# Costume_Controller_Base_Board.net
KiCad netlist of a schematic drawn in EAGLE
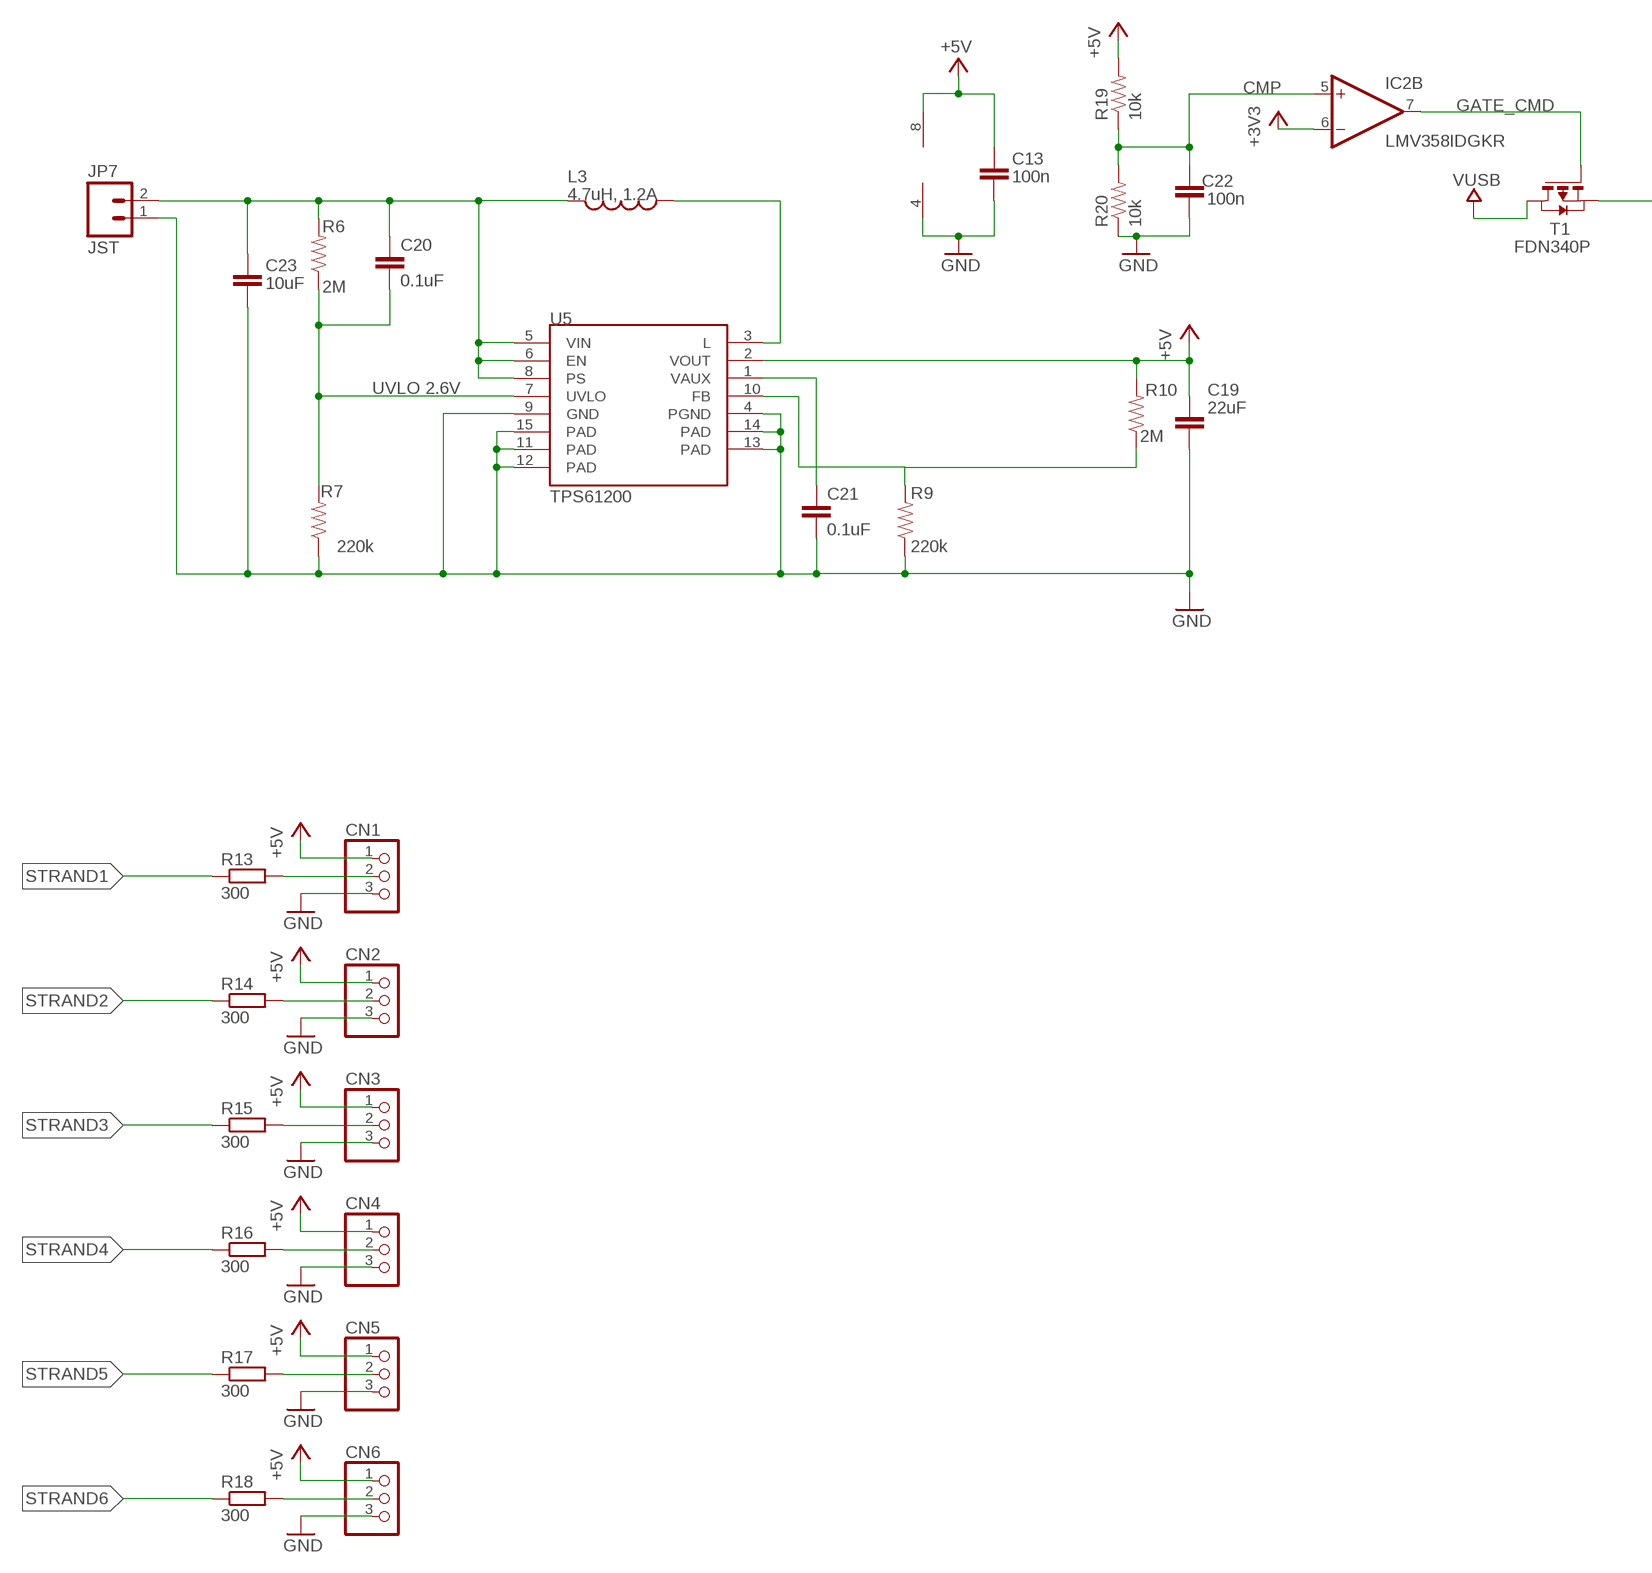
[diagram p0: schematic, sheet 1, part 1 of 2]
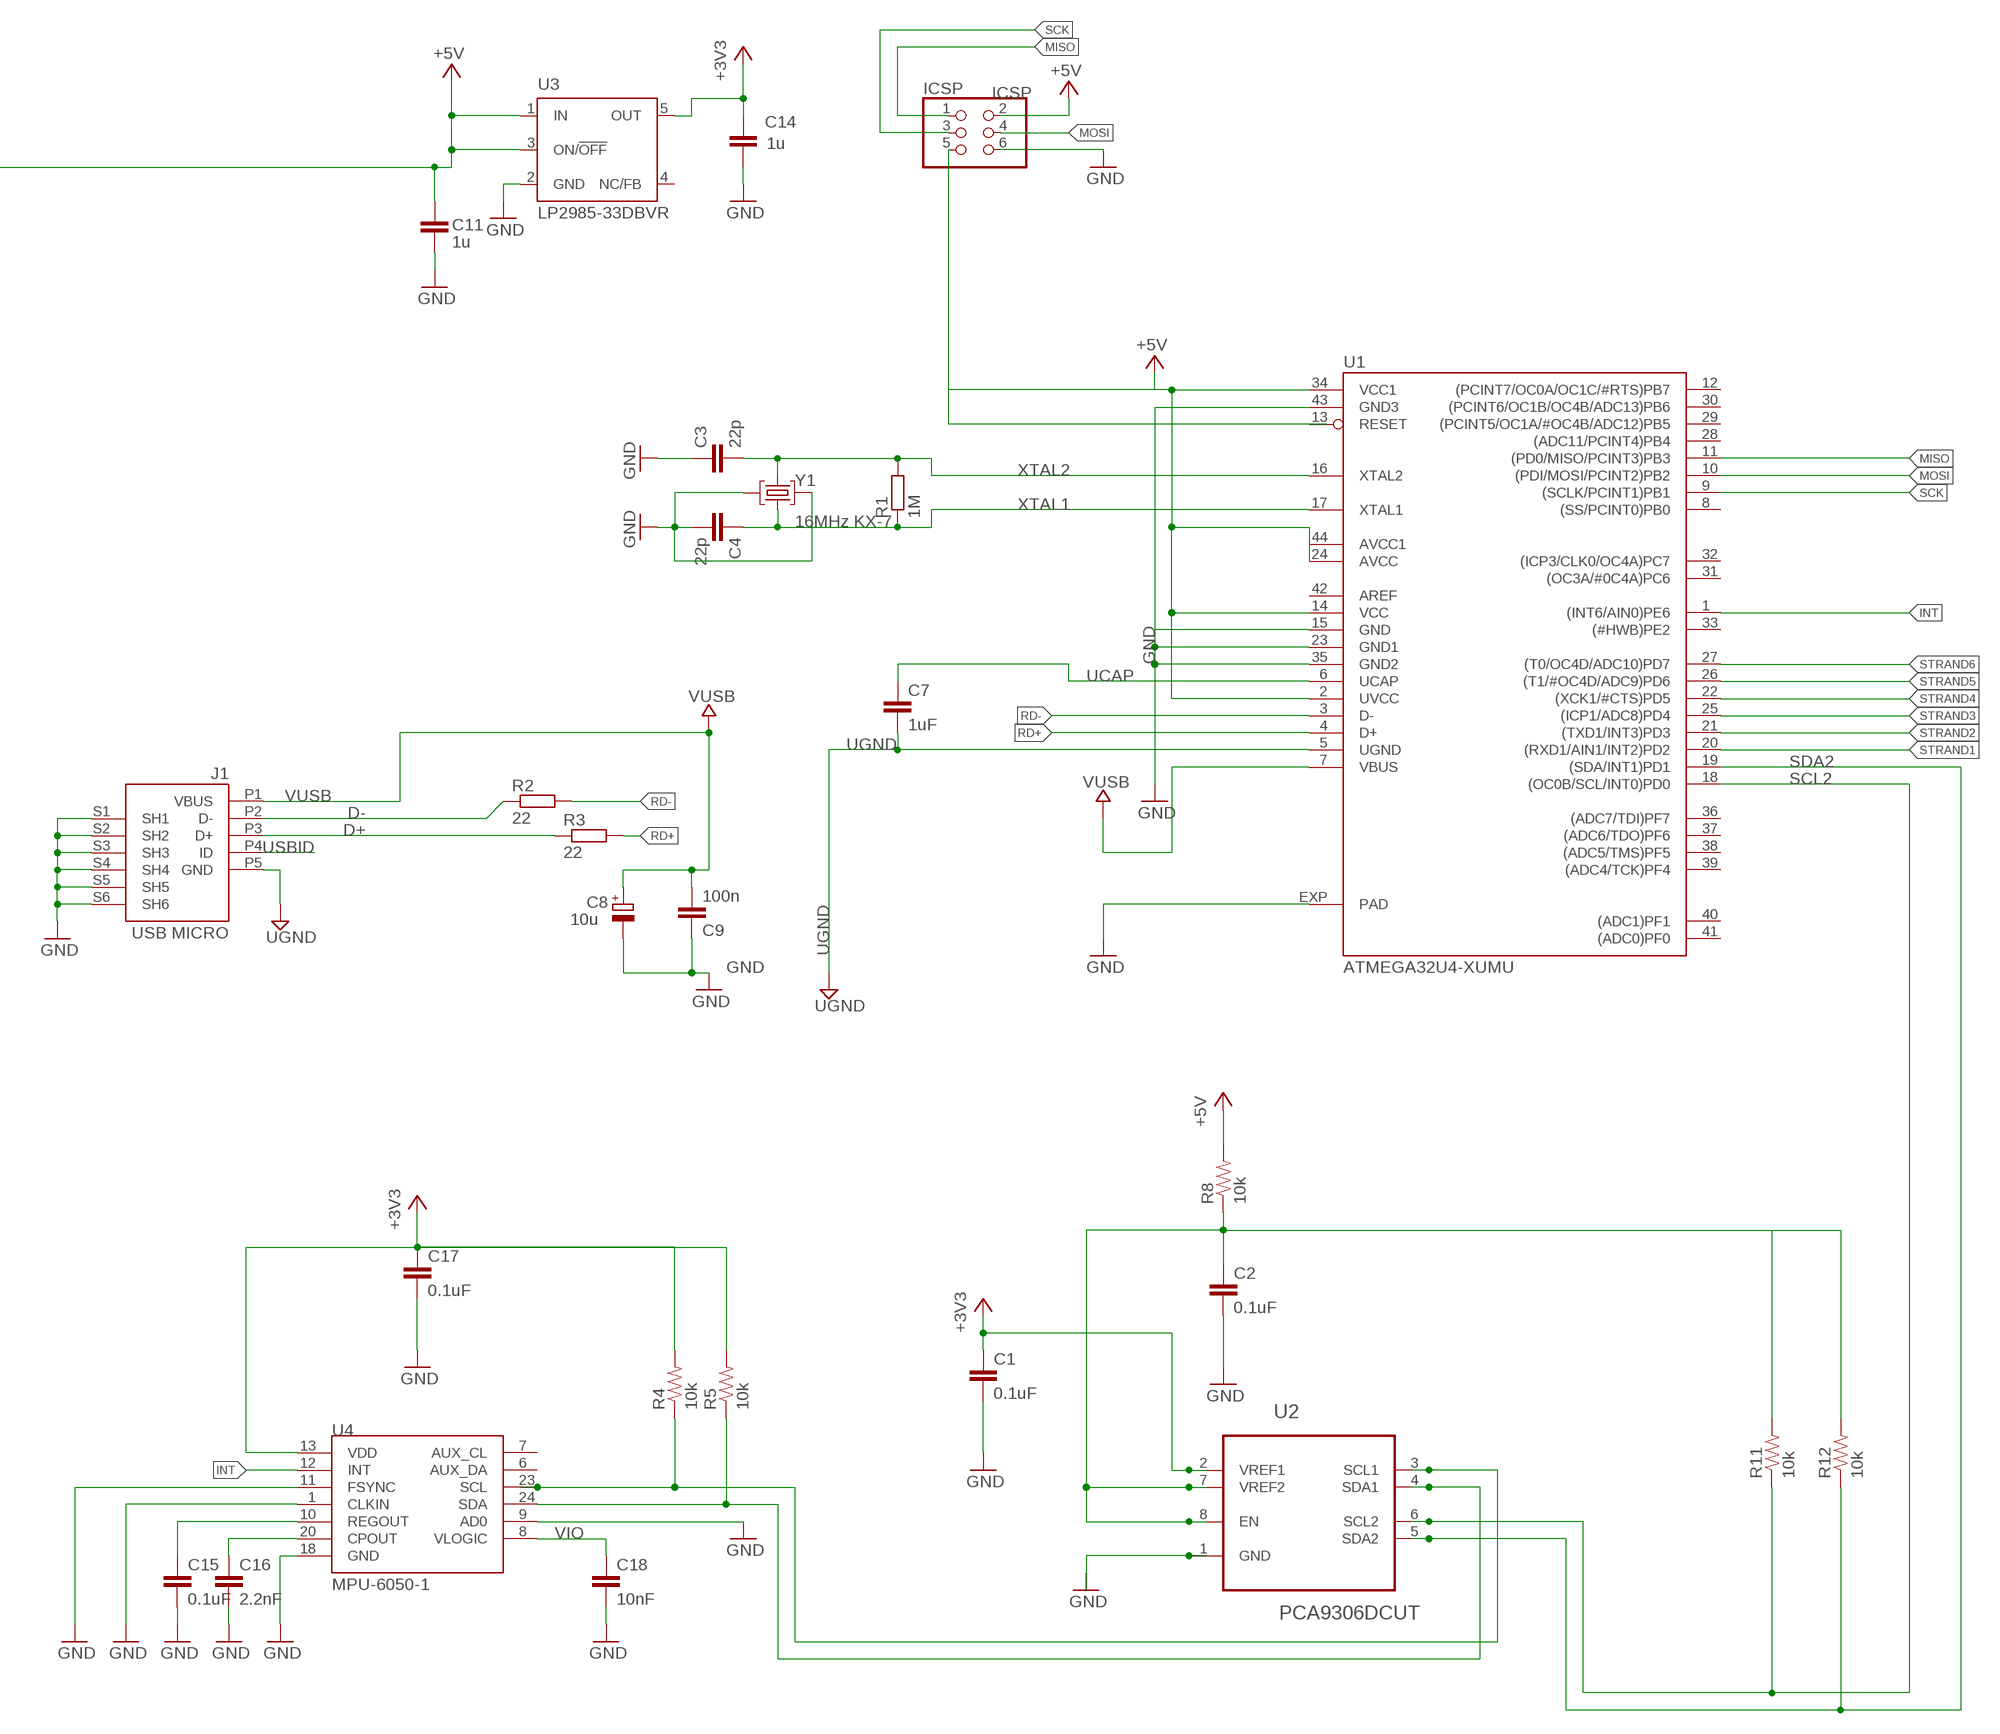
[diagram p1: schematic, sheet 1, part 2 of 2]

(export (version "E")
  (design (tool "Eeschema 10.0.6"))
  (components
    (comp (ref "C1")
      (value "0.1uF")
      (footprint "eagle-import:0603-CAP")
      (libsource (lib "eagle-import") (part "CAP0603-CAP"))
    )
    (comp (ref "C2")
      (value "0.1uF")
      (footprint "eagle-import:0603-CAP")
      (libsource (lib "eagle-import") (part "CAP0603-CAP"))
    )
    (comp (ref "C3")
      (value "22p")
      (footprint "eagle-import:C0603-ROUND")
      (libsource (lib "eagle-import") (part "C-EUC0603"))
    )
    (comp (ref "C4")
      (value "22p")
      (footprint "eagle-import:C0603-ROUND")
      (libsource (lib "eagle-import") (part "C-EUC0603"))
    )
    (comp (ref "C7")
      (value "1uF")
      (footprint "eagle-import:C0603-ROUND")
      (libsource (lib "eagle-import") (part "C-EUC0603"))
    )
    (comp (ref "C8")
      (value "10u")
      (footprint "eagle-import:SMC_B")
      (libsource (lib "eagle-import") (part "CPOL-EUSMCB"))
    )
    (comp (ref "C9")
      (value "100n")
      (footprint "eagle-import:C0603-ROUND")
      (libsource (lib "eagle-import") (part "C-EUC0603"))
    )
    (comp (ref "C11")
      (value "1u")
      (footprint "eagle-import:C0603-ROUND")
      (libsource (lib "eagle-import") (part "C-EUC0603"))
    )
    (comp (ref "C13")
      (value "100n")
      (footprint "eagle-import:C0603-ROUND")
      (libsource (lib "eagle-import") (part "C-EUC0603"))
    )
    (comp (ref "C14")
      (value "1u")
      (footprint "eagle-import:C0603-ROUND")
      (libsource (lib "eagle-import") (part "C-EUC0603"))
    )
    (comp (ref "C15")
      (value "0.1uF")
      (footprint "eagle-import:0603-CAP")
      (libsource (lib "eagle-import") (part "CAP0603-CAP"))
    )
    (comp (ref "C16")
      (value "2.2nF")
      (footprint "eagle-import:0603-CAP")
      (libsource (lib "eagle-import") (part "CAP0603-CAP"))
    )
    (comp (ref "C17")
      (value "0.1uF")
      (footprint "eagle-import:0603-CAP")
      (libsource (lib "eagle-import") (part "CAP0603-CAP"))
    )
    (comp (ref "C18")
      (value "10nF")
      (footprint "eagle-import:0603-CAP")
      (libsource (lib "eagle-import") (part "CAP0603-CAP"))
    )
    (comp (ref "C19")
      (value "22uF")
      (footprint "eagle-import:C0603")
      (libsource (lib "eagle-import") (part "resistor_C-EUC0603"))
    )
    (comp (ref "C20")
      (value "0.1uF")
      (footprint "eagle-import:0603-CAP")
      (libsource (lib "eagle-import") (part "CAP0603-CAP"))
    )
    (comp (ref "C21")
      (value "0.1uF")
      (footprint "eagle-import:0603-CAP")
      (libsource (lib "eagle-import") (part "CAP0603-CAP"))
    )
    (comp (ref "C22")
      (value "100n")
      (footprint "eagle-import:C0603-ROUND")
      (libsource (lib "eagle-import") (part "C-EUC0603"))
    )
    (comp (ref "C23")
      (value "10uF")
      (footprint "eagle-import:1206")
      (libsource (lib "eagle-import") (part "CAP1206"))
    )
    (comp (ref "CN1")
      (value "JST_3PIN")
      (footprint "eagle-import:JSTPH3")
      (libsource (lib "eagle-import") (part "JST_3PIN"))
    )
    (comp (ref "CN2")
      (value "JST_3PIN")
      (footprint "eagle-import:JSTPH3")
      (libsource (lib "eagle-import") (part "JST_3PIN"))
    )
    (comp (ref "CN3")
      (value "JST_3PIN")
      (footprint "eagle-import:JSTPH3")
      (libsource (lib "eagle-import") (part "JST_3PIN"))
    )
    (comp (ref "CN4")
      (value "JST_3PIN")
      (footprint "eagle-import:JSTPH3")
      (libsource (lib "eagle-import") (part "JST_3PIN"))
    )
    (comp (ref "CN5")
      (value "JST_3PIN")
      (footprint "eagle-import:JSTPH3")
      (libsource (lib "eagle-import") (part "JST_3PIN"))
    )
    (comp (ref "CN6")
      (value "JST_3PIN")
      (footprint "eagle-import:JSTPH3")
      (libsource (lib "eagle-import") (part "JST_3PIN"))
    )
    (comp (ref "IC2")
      (value "LMV358IDGKR")
      (footprint "eagle-import:MSOP08")
      (libsource (lib "eagle-import") (part "LMV358?MMX"))
    )
    (comp (ref "ICSP")
      (value "ICSP")
      (footprint "eagle-import:2X03")
      (libsource (lib "eagle-import") (part "PINHD-2X3"))
    )
    (comp (ref "J1")
      (value "USB MICRO")
      (footprint "eagle-import:CON2_USB_MICRO_B_AT")
      (libsource (lib "eagle-import") (part "MYCON2_USB-MINI-B"))
    )
    (comp (ref "JP7")
      (value "JST")
      (footprint "eagle-import:JST-2-SMD")
      (libsource (lib "eagle-import") (part "M02-JST-2MM-SMT"))
    )
    (comp (ref "L3")
      (value "4.7uH, 1.2A")
      (footprint "eagle-import:CDRH2D09")
      (libsource (lib "eagle-import") (part "INDUCTOR."))
    )
    (comp (ref "R1")
      (value "1M")
      (footprint "eagle-import:R0603")
      (libsource (lib "eagle-import") (part "R-EU_R0603"))
    )
    (comp (ref "R2")
      (value "22")
      (footprint "eagle-import:R0603")
      (libsource (lib "eagle-import") (part "R-EU_R0603"))
    )
    (comp (ref "R3")
      (value "22")
      (footprint "eagle-import:R0603")
      (libsource (lib "eagle-import") (part "R-EU_R0603"))
    )
    (comp (ref "R4")
      (value "10k")
      (footprint "eagle-import:0603-RES")
      (libsource (lib "eagle-import") (part "RESISTOR0603-RES"))
    )
    (comp (ref "R5")
      (value "10k")
      (footprint "eagle-import:0603-RES")
      (libsource (lib "eagle-import") (part "RESISTOR0603-RES"))
    )
    (comp (ref "R6")
      (value "2M")
      (footprint "eagle-import:0603-RES")
      (libsource (lib "eagle-import") (part "RESISTOR0603-RES"))
    )
    (comp (ref "R7")
      (value "220k")
      (footprint "eagle-import:0603-RES")
      (libsource (lib "eagle-import") (part "RESISTOR0603-RES"))
    )
    (comp (ref "R8")
      (value "10k")
      (footprint "eagle-import:0603-RES")
      (libsource (lib "eagle-import") (part "RESISTOR0603-RES"))
    )
    (comp (ref "R9")
      (value "220k")
      (footprint "eagle-import:0603-RES")
      (libsource (lib "eagle-import") (part "RESISTOR0603-RES"))
    )
    (comp (ref "R10")
      (value "2M")
      (footprint "eagle-import:0603-RES")
      (libsource (lib "eagle-import") (part "RESISTOR0603-RES"))
    )
    (comp (ref "R11")
      (value "10k")
      (footprint "eagle-import:0603-RES")
      (libsource (lib "eagle-import") (part "RESISTOR0603-RES"))
    )
    (comp (ref "R12")
      (value "10k")
      (footprint "eagle-import:0603-RES")
      (libsource (lib "eagle-import") (part "RESISTOR0603-RES"))
    )
    (comp (ref "R13")
      (value "300")
      (footprint "eagle-import:R0603")
      (libsource (lib "eagle-import") (part "R-EU_R0603"))
    )
    (comp (ref "R14")
      (value "300")
      (footprint "eagle-import:R0603")
      (libsource (lib "eagle-import") (part "R-EU_R0603"))
    )
    (comp (ref "R15")
      (value "300")
      (footprint "eagle-import:R0603")
      (libsource (lib "eagle-import") (part "R-EU_R0603"))
    )
    (comp (ref "R16")
      (value "300")
      (footprint "eagle-import:R0603")
      (libsource (lib "eagle-import") (part "R-EU_R0603"))
    )
    (comp (ref "R17")
      (value "300")
      (footprint "eagle-import:R0603")
      (libsource (lib "eagle-import") (part "R-EU_R0603"))
    )
    (comp (ref "R18")
      (value "300")
      (footprint "eagle-import:R0603")
      (libsource (lib "eagle-import") (part "R-EU_R0603"))
    )
    (comp (ref "R19")
      (value "10k")
      (footprint "eagle-import:0603-RES")
      (libsource (lib "eagle-import") (part "RESISTOR0603-RES"))
    )
    (comp (ref "R20")
      (value "10k")
      (footprint "eagle-import:0603-RES")
      (libsource (lib "eagle-import") (part "RESISTOR0603-RES"))
    )
    (comp (ref "T1")
      (value "FDN340P")
      (footprint "eagle-import:SOT-23")
      (libsource (lib "eagle-import") (part "PMOSSOT23"))
    )
    (comp (ref "U1")
      (value "ATMEGA32U4-XUMU")
      (footprint "eagle-import:QFN44ML7X7")
      (libsource (lib "eagle-import") (part "ATMEGA32U4-XUMU"))
    )
    (comp (ref "U2")
      (value "PCA9306DCUT")
      (footprint "eagle-import:SOP50P310X90-8N")
      (libsource (lib "eagle-import") (part "PCA9306DCUT"))
    )
    (comp (ref "U3")
      (value "LP2985-33DBVR")
      (footprint "eagle-import:SOT23-DBV")
      (libsource (lib "eagle-import") (part "LP2985-XXDBVR33"))
    )
    (comp (ref "U4")
      (value "MPU-6050-1")
      (footprint "eagle-import:QFN-24-4MM2")
      (libsource (lib "eagle-import") (part "MPU-6050-1"))
    )
    (comp (ref "U5")
      (value "TPS61200")
      (footprint "eagle-import:QFN-10_PAD")
      (libsource (lib "eagle-import") (part "TPS61200"))
    )
    (comp (ref "Y1")
      (value "16MHz KX-7")
      (footprint "eagle-import:CRYSTAL-3.2-2.5")
      (libsource (lib "eagle-import") (part "CRYSTAL-3.2-2.5"))
    )
  )
  (nets
    (net (code "1") (name "+3V3") (class "Default")
      (node (ref "C1") (pin "1") (pinfunction "1_1") (pintype "passive"))
      (node (ref "C14") (pin "2") (pinfunction "2_2") (pintype "passive"))
      (node (ref "C17") (pin "1") (pinfunction "1_1") (pintype "passive"))
      (node (ref "IC2") (pin "6") (pinfunction "-IN_6") (pintype "input"))
      (node (ref "R4") (pin "2") (pinfunction "2_2") (pintype "passive"))
      (node (ref "R5") (pin "2") (pinfunction "2_2") (pintype "passive"))
      (node (ref "U2") (pin "2") (pinfunction "VREF1_2") (pintype "power_in"))
      (node (ref "U3") (pin "5") (pinfunction "OUT_5") (pintype "passive"))
      (node (ref "U4") (pin "13") (pinfunction "VDD_13") (pintype "bidirectional"))
    )
    (net (code "2") (name "+5V") (class "Default")
      (node (ref "C11") (pin "2") (pinfunction "2_2") (pintype "passive"))
      (node (ref "C13") (pin "1") (pinfunction "1_1") (pintype "passive"))
      (node (ref "C19") (pin "1") (pinfunction "1_1") (pintype "passive"))
      (node (ref "CN1") (pin "1") (pinfunction "1_1") (pintype "passive"))
      (node (ref "CN2") (pin "1") (pinfunction "1_1") (pintype "passive"))
      (node (ref "CN3") (pin "1") (pinfunction "1_1") (pintype "passive"))
      (node (ref "CN4") (pin "1") (pinfunction "1_1") (pintype "passive"))
      (node (ref "CN5") (pin "1") (pinfunction "1_1") (pintype "passive"))
      (node (ref "CN6") (pin "1") (pinfunction "1_1") (pintype "passive"))
      (node (ref "IC2") (pin "8") (pinfunction "V+_8") (pintype "power_in"))
      (node (ref "ICSP") (pin "2") (pinfunction "2_2") (pintype "passive"))
      (node (ref "ICSP") (pin "5") (pinfunction "5_5") (pintype "passive"))
      (node (ref "R10") (pin "2") (pinfunction "2_2") (pintype "passive"))
      (node (ref "R19") (pin "2") (pinfunction "2_2") (pintype "passive"))
      (node (ref "R8") (pin "2") (pinfunction "2_2") (pintype "passive"))
      (node (ref "T1") (pin "2") (pinfunction "S_2") (pintype "passive"))
      (node (ref "U1") (pin "14") (pinfunction "VCC_14") (pintype "power_in"))
      (node (ref "U1") (pin "2") (pinfunction "UVCC_2") (pintype "power_in"))
      (node (ref "U1") (pin "24") (pinfunction "AVCC_24") (pintype "power_in"))
      (node (ref "U1") (pin "34") (pinfunction "VCC1_34") (pintype "power_in"))
      (node (ref "U1") (pin "44") (pinfunction "AVCC1_44") (pintype "power_in"))
      (node (ref "U3") (pin "1") (pinfunction "IN_1") (pintype "input"))
      (node (ref "U3") (pin "3") (pinfunction "ON/~{OFF}_3") (pintype "input"))
      (node (ref "U5") (pin "2") (pinfunction "VOUT_2") (pintype "passive"))
    )
    (net (code "3") (name "/AREF") (class "Default")
      (node (ref "U1") (pin "42") (pinfunction "AREF_42") (pintype "power_in"))
    )
    (net (code "4") (name "/CMP") (class "Default")
      (node (ref "C22") (pin "2") (pinfunction "2_2") (pintype "passive"))
      (node (ref "IC2") (pin "5") (pinfunction "+IN_5") (pintype "input"))
      (node (ref "R19") (pin "1") (pinfunction "1_1") (pintype "passive"))
      (node (ref "R20") (pin "2") (pinfunction "2_2") (pintype "passive"))
    )
    (net (code "5") (name "/D+") (class "Default")
      (node (ref "J1") (pin "P3") (pinfunction "D+_P3") (pintype "bidirectional"))
      (node (ref "R3") (pin "1") (pinfunction "1_1") (pintype "passive"))
    )
    (net (code "6") (name "/D-") (class "Default")
      (node (ref "J1") (pin "P2") (pinfunction "D-_P2") (pintype "bidirectional"))
      (node (ref "R2") (pin "1") (pinfunction "1_1") (pintype "passive"))
    )
    (net (code "7") (name "/GATE_CMD") (class "Default")
      (node (ref "IC2") (pin "7") (pinfunction "OUT_7") (pintype "output"))
      (node (ref "T1") (pin "3") (pinfunction "G_3") (pintype "passive"))
    )
    (net (code "8") (name "/SCL2") (class "Default")
      (node (ref "R11") (pin "1") (pinfunction "1_1") (pintype "passive"))
      (node (ref "U1") (pin "18") (pinfunction "(OC0B/SCL/INT0)PD0_18") (pintype "bidirectional"))
      (node (ref "U2") (pin "6") (pinfunction "SCL2_6") (pintype "bidirectional"))
    )
    (net (code "9") (name "/SDA2") (class "Default")
      (node (ref "R12") (pin "1") (pinfunction "1_1") (pintype "passive"))
      (node (ref "U1") (pin "19") (pinfunction "(SDA/INT1)PD1_19") (pintype "bidirectional"))
      (node (ref "U2") (pin "5") (pinfunction "SDA2_5") (pintype "bidirectional"))
    )
    (net (code "10") (name "/UCAP") (class "Default")
      (node (ref "C7") (pin "1") (pinfunction "1_1") (pintype "passive"))
      (node (ref "U1") (pin "6") (pinfunction "UCAP_6") (pintype "passive"))
    )
    (net (code "11") (name "/USBID") (class "Default")
      (node (ref "J1") (pin "P4") (pinfunction "ID_P4") (pintype "bidirectional"))
    )
    (net (code "12") (name "/VIO") (class "Default")
      (node (ref "C18") (pin "1") (pinfunction "1_1") (pintype "passive"))
      (node (ref "U4") (pin "8") (pinfunction "VLOGIC_8") (pintype "bidirectional"))
    )
    (net (code "13") (name "/XTAL1") (class "Default")
      (node (ref "C4") (pin "1") (pinfunction "1_1") (pintype "passive"))
      (node (ref "R1") (pin "1") (pinfunction "1_1") (pintype "passive"))
      (node (ref "U1") (pin "17") (pinfunction "XTAL1_17") (pintype "bidirectional"))
      (node (ref "Y1") (pin "1") (pinfunction "C1_1") (pintype "passive"))
    )
    (net (code "14") (name "/XTAL2") (class "Default")
      (node (ref "C3") (pin "2") (pinfunction "2_2") (pintype "passive"))
      (node (ref "R1") (pin "2") (pinfunction "2_2") (pintype "passive"))
      (node (ref "U1") (pin "16") (pinfunction "XTAL2_16") (pintype "bidirectional"))
      (node (ref "Y1") (pin "3") (pinfunction "C2_3") (pintype "passive"))
    )
    (net (code "15") (name "GND") (class "Default")
      (node (ref "C1") (pin "2") (pinfunction "2_2") (pintype "passive"))
      (node (ref "C11") (pin "1") (pinfunction "1_1") (pintype "passive"))
      (node (ref "C13") (pin "2") (pinfunction "2_2") (pintype "passive"))
      (node (ref "C14") (pin "1") (pinfunction "1_1") (pintype "passive"))
      (node (ref "C15") (pin "2") (pinfunction "2_2") (pintype "passive"))
      (node (ref "C16") (pin "2") (pinfunction "2_2") (pintype "passive"))
      (node (ref "C17") (pin "2") (pinfunction "2_2") (pintype "passive"))
      (node (ref "C18") (pin "2") (pinfunction "2_2") (pintype "passive"))
      (node (ref "C19") (pin "2") (pinfunction "2_2") (pintype "passive"))
      (node (ref "C2") (pin "2") (pinfunction "2_2") (pintype "passive"))
      (node (ref "C21") (pin "2") (pinfunction "2_2") (pintype "passive"))
      (node (ref "C22") (pin "1") (pinfunction "1_1") (pintype "passive"))
      (node (ref "C23") (pin "2") (pinfunction "2_2") (pintype "passive"))
      (node (ref "C3") (pin "1") (pinfunction "1_1") (pintype "passive"))
      (node (ref "C4") (pin "2") (pinfunction "2_2") (pintype "passive"))
      (node (ref "C8") (pin "-") (pinfunction "-_-") (pintype "passive"))
      (node (ref "C9") (pin "1") (pinfunction "1_1") (pintype "passive"))
      (node (ref "CN1") (pin "3") (pinfunction "3_3") (pintype "passive"))
      (node (ref "CN2") (pin "3") (pinfunction "3_3") (pintype "passive"))
      (node (ref "CN3") (pin "3") (pinfunction "3_3") (pintype "passive"))
      (node (ref "CN4") (pin "3") (pinfunction "3_3") (pintype "passive"))
      (node (ref "CN5") (pin "3") (pinfunction "3_3") (pintype "passive"))
      (node (ref "CN6") (pin "3") (pinfunction "3_3") (pintype "passive"))
      (node (ref "IC2") (pin "4") (pinfunction "V-_4") (pintype "power_in"))
      (node (ref "ICSP") (pin "6") (pinfunction "6_6") (pintype "passive"))
      (node (ref "J1") (pin "S1") (pinfunction "SH1_S1") (pintype "passive"))
      (node (ref "J1") (pin "S2") (pinfunction "SH2_S2") (pintype "passive"))
      (node (ref "J1") (pin "S3") (pinfunction "SH3_S3") (pintype "passive"))
      (node (ref "J1") (pin "S4") (pinfunction "SH4_S4") (pintype "passive"))
      (node (ref "J1") (pin "S5") (pinfunction "SH5_S5") (pintype "passive"))
      (node (ref "J1") (pin "S6") (pinfunction "SH6_S6") (pintype "passive"))
      (node (ref "JP7") (pin "1") (pinfunction "1_1") (pintype "passive"))
      (node (ref "R20") (pin "1") (pinfunction "1_1") (pintype "passive"))
      (node (ref "R7") (pin "1") (pinfunction "1_1") (pintype "passive"))
      (node (ref "R9") (pin "1") (pinfunction "1_1") (pintype "passive"))
      (node (ref "U1") (pin "15") (pinfunction "GND_15") (pintype "power_in"))
      (node (ref "U1") (pin "23") (pinfunction "GND1_23") (pintype "power_in"))
      (node (ref "U1") (pin "35") (pinfunction "GND2_35") (pintype "power_in"))
      (node (ref "U1") (pin "43") (pinfunction "GND3_43") (pintype "power_in"))
      (node (ref "U1") (pin "EXP") (pinfunction "PAD_EXP") (pintype "power_in"))
      (node (ref "U2") (pin "1") (pinfunction "GND_1") (pintype "passive"))
      (node (ref "U3") (pin "2") (pinfunction "GND_2") (pintype "power_in"))
      (node (ref "U4") (pin "1") (pinfunction "CLKIN_1") (pintype "bidirectional"))
      (node (ref "U4") (pin "11") (pinfunction "FSYNC_11") (pintype "bidirectional"))
      (node (ref "U4") (pin "18") (pinfunction "GND_18") (pintype "bidirectional"))
      (node (ref "U4") (pin "9") (pinfunction "AD0_9") (pintype "bidirectional"))
      (node (ref "U5") (pin "11") (pinfunction "PAD_11") (pintype "power_in"))
      (node (ref "U5") (pin "12") (pinfunction "PAD_12") (pintype "power_in"))
      (node (ref "U5") (pin "13") (pinfunction "PAD_13") (pintype "power_in"))
      (node (ref "U5") (pin "14") (pinfunction "PAD_14") (pintype "power_in"))
      (node (ref "U5") (pin "15") (pinfunction "PAD_15") (pintype "power_in"))
      (node (ref "U5") (pin "4") (pinfunction "PGND_4") (pintype "power_in"))
      (node (ref "U5") (pin "9") (pinfunction "GND_9") (pintype "power_in"))
      (node (ref "Y1") (pin "2") (pinfunction "GND_2") (pintype "passive"))
      (node (ref "Y1") (pin "4") (pinfunction "GND_4") (pintype "passive"))
    )
    (net (code "16") (name "INT") (class "Default")
      (node (ref "U1") (pin "1") (pinfunction "(INT6/AIN0)PE6_1") (pintype "bidirectional"))
      (node (ref "U4") (pin "12") (pinfunction "INT_12") (pintype "bidirectional"))
    )
    (net (code "17") (name "MISO") (class "Default")
      (node (ref "ICSP") (pin "1") (pinfunction "1_1") (pintype "passive"))
      (node (ref "U1") (pin "11") (pinfunction "(PD0/MISO/PCINT3)PB3_11") (pintype "bidirectional"))
    )
    (net (code "18") (name "MOSI") (class "Default")
      (node (ref "ICSP") (pin "4") (pinfunction "4_4") (pintype "passive"))
      (node (ref "U1") (pin "10") (pinfunction "(PDI/MOSI/PCINT2)PB2_10") (pintype "bidirectional"))
    )
    (net (code "19") (name "Net-(CN1-Pad2)") (class "Default")
      (node (ref "CN1") (pin "2") (pinfunction "2_2") (pintype "passive"))
      (node (ref "R13") (pin "2") (pinfunction "2_2") (pintype "passive"))
    )
    (net (code "20") (name "Net-(CN2-Pad2)") (class "Default")
      (node (ref "CN2") (pin "2") (pinfunction "2_2") (pintype "passive"))
      (node (ref "R14") (pin "2") (pinfunction "2_2") (pintype "passive"))
    )
    (net (code "21") (name "Net-(CN3-Pad2)") (class "Default")
      (node (ref "CN3") (pin "2") (pinfunction "2_2") (pintype "passive"))
      (node (ref "R15") (pin "2") (pinfunction "2_2") (pintype "passive"))
    )
    (net (code "22") (name "Net-(CN4-Pad2)") (class "Default")
      (node (ref "CN4") (pin "2") (pinfunction "2_2") (pintype "passive"))
      (node (ref "R16") (pin "2") (pinfunction "2_2") (pintype "passive"))
    )
    (net (code "23") (name "Net-(CN5-Pad2)") (class "Default")
      (node (ref "CN5") (pin "2") (pinfunction "2_2") (pintype "passive"))
      (node (ref "R17") (pin "2") (pinfunction "2_2") (pintype "passive"))
    )
    (net (code "24") (name "Net-(CN6-Pad2)") (class "Default")
      (node (ref "CN6") (pin "2") (pinfunction "2_2") (pintype "passive"))
      (node (ref "R18") (pin "2") (pinfunction "2_2") (pintype "passive"))
    )
    (net (code "25") (name "Net-(L3-1)") (class "Default")
      (node (ref "L3") (pin "P$1") (pinfunction "1_P$1") (pintype "passive"))
      (node (ref "U5") (pin "3") (pinfunction "L_3") (pintype "passive"))
    )
    (net (code "26") (name "Net-(L3-2)") (class "Default")
      (node (ref "C20") (pin "1") (pinfunction "1_1") (pintype "passive"))
      (node (ref "C23") (pin "1") (pinfunction "1_1") (pintype "passive"))
      (node (ref "JP7") (pin "2") (pinfunction "2_2") (pintype "passive"))
      (node (ref "L3") (pin "P$2") (pinfunction "2_P$2") (pintype "passive"))
      (node (ref "R6") (pin "2") (pinfunction "2_2") (pintype "passive"))
      (node (ref "U5") (pin "5") (pinfunction "VIN_5") (pintype "power_in"))
      (node (ref "U5") (pin "6") (pinfunction "EN_6") (pintype "input"))
      (node (ref "U5") (pin "8") (pinfunction "PS_8") (pintype "input"))
    )
    (net (code "27") (name "Net-(U2-EN)") (class "Default")
      (node (ref "C2") (pin "1") (pinfunction "1_1") (pintype "passive"))
      (node (ref "R11") (pin "2") (pinfunction "2_2") (pintype "passive"))
      (node (ref "R12") (pin "2") (pinfunction "2_2") (pintype "passive"))
      (node (ref "R8") (pin "1") (pinfunction "1_1") (pintype "passive"))
      (node (ref "U2") (pin "7") (pinfunction "VREF2_7") (pintype "power_in"))
      (node (ref "U2") (pin "8") (pinfunction "EN_8") (pintype "input"))
    )
    (net (code "28") (name "Net-(U2-SCL1)") (class "Default")
      (node (ref "R4") (pin "1") (pinfunction "1_1") (pintype "passive"))
      (node (ref "U2") (pin "3") (pinfunction "SCL1_3") (pintype "bidirectional"))
      (node (ref "U4") (pin "23") (pinfunction "SCL_23") (pintype "bidirectional"))
    )
    (net (code "29") (name "Net-(U2-SDA1)") (class "Default")
      (node (ref "R5") (pin "1") (pinfunction "1_1") (pintype "passive"))
      (node (ref "U2") (pin "4") (pinfunction "SDA1_4") (pintype "bidirectional"))
      (node (ref "U4") (pin "24") (pinfunction "SDA_24") (pintype "bidirectional"))
    )
    (net (code "30") (name "Net-(U4-CPOUT)") (class "Default")
      (node (ref "C16") (pin "1") (pinfunction "1_1") (pintype "passive"))
      (node (ref "U4") (pin "20") (pinfunction "CPOUT_20") (pintype "bidirectional"))
    )
    (net (code "31") (name "Net-(U4-REGOUT)") (class "Default")
      (node (ref "C15") (pin "1") (pinfunction "1_1") (pintype "passive"))
      (node (ref "U4") (pin "10") (pinfunction "REGOUT_10") (pintype "bidirectional"))
    )
    (net (code "32") (name "Net-(U5-FB)") (class "Default")
      (node (ref "R10") (pin "1") (pinfunction "1_1") (pintype "passive"))
      (node (ref "R9") (pin "2") (pinfunction "2_2") (pintype "passive"))
      (node (ref "U5") (pin "10") (pinfunction "FB_10") (pintype "passive"))
    )
    (net (code "33") (name "Net-(U5-UVLO)") (class "Default")
      (node (ref "C20") (pin "2") (pinfunction "2_2") (pintype "passive"))
      (node (ref "R6") (pin "1") (pinfunction "1_1") (pintype "passive"))
      (node (ref "R7") (pin "2") (pinfunction "2_2") (pintype "passive"))
      (node (ref "U5") (pin "7") (pinfunction "UVLO_7") (pintype "passive"))
    )
    (net (code "34") (name "Net-(U5-VAUX)") (class "Default")
      (node (ref "C21") (pin "1") (pinfunction "1_1") (pintype "passive"))
      (node (ref "U5") (pin "1") (pinfunction "VAUX_1") (pintype "passive"))
    )
    (net (code "35") (name "RD+") (class "Default")
      (node (ref "R3") (pin "2") (pinfunction "2_2") (pintype "passive"))
      (node (ref "U1") (pin "4") (pinfunction "D+_4") (pintype "bidirectional"))
    )
    (net (code "36") (name "RD-") (class "Default")
      (node (ref "R2") (pin "2") (pinfunction "2_2") (pintype "passive"))
      (node (ref "U1") (pin "3") (pinfunction "D-_3") (pintype "bidirectional"))
    )
    (net (code "37") (name "SCK") (class "Default")
      (node (ref "ICSP") (pin "3") (pinfunction "3_3") (pintype "passive"))
      (node (ref "U1") (pin "9") (pinfunction "(SCLK/PCINT1)PB1_9") (pintype "bidirectional"))
    )
    (net (code "38") (name "STRAND1") (class "Default")
      (node (ref "R13") (pin "1") (pinfunction "1_1") (pintype "passive"))
      (node (ref "U1") (pin "20") (pinfunction "(RXD1/AIN1/INT2)PD2_20") (pintype "bidirectional"))
    )
    (net (code "39") (name "STRAND2") (class "Default")
      (node (ref "R14") (pin "1") (pinfunction "1_1") (pintype "passive"))
      (node (ref "U1") (pin "21") (pinfunction "(TXD1/INT3)PD3_21") (pintype "bidirectional"))
    )
    (net (code "40") (name "STRAND3") (class "Default")
      (node (ref "R15") (pin "1") (pinfunction "1_1") (pintype "passive"))
      (node (ref "U1") (pin "25") (pinfunction "(ICP1/ADC8)PD4_25") (pintype "bidirectional"))
    )
    (net (code "41") (name "STRAND4") (class "Default")
      (node (ref "R16") (pin "1") (pinfunction "1_1") (pintype "passive"))
      (node (ref "U1") (pin "22") (pinfunction "(XCK1/#CTS)PD5_22") (pintype "bidirectional"))
    )
    (net (code "42") (name "STRAND5") (class "Default")
      (node (ref "R17") (pin "1") (pinfunction "1_1") (pintype "passive"))
      (node (ref "U1") (pin "26") (pinfunction "(T1/#OC4D/ADC9)PD6_26") (pintype "bidirectional"))
    )
    (net (code "43") (name "STRAND6") (class "Default")
      (node (ref "R18") (pin "1") (pinfunction "1_1") (pintype "passive"))
      (node (ref "U1") (pin "27") (pinfunction "(T0/OC4D/ADC10)PD7_27") (pintype "bidirectional"))
    )
    (net (code "44") (name "UGND") (class "Default")
      (node (ref "C7") (pin "2") (pinfunction "2_2") (pintype "passive"))
      (node (ref "J1") (pin "P5") (pinfunction "GND_P5") (pintype "passive"))
      (node (ref "U1") (pin "5") (pinfunction "UGND_5") (pintype "power_in"))
    )
    (net (code "45") (name "VUSB") (class "Default")
      (node (ref "C8") (pin "+") (pinfunction "+_+") (pintype "passive"))
      (node (ref "C9") (pin "2") (pinfunction "2_2") (pintype "passive"))
      (node (ref "J1") (pin "P1") (pinfunction "VBUS_P1") (pintype "power_in"))
      (node (ref "T1") (pin "1") (pinfunction "D_1") (pintype "passive"))
      (node (ref "U1") (pin "7") (pinfunction "VBUS_7") (pintype "input"))
    )
    (net (code "46") (name "unconnected-(U1-(#HWB)PE2-Pad33)") (class "Default")
      (node (ref "U1") (pin "33") (pinfunction "(#HWB)PE2_33") (pintype "bidirectional"))
    )
    (net (code "47") (name "unconnected-(U1-(ADC0)PF0-Pad41)") (class "Default")
      (node (ref "U1") (pin "41") (pinfunction "(ADC0)PF0_41") (pintype "bidirectional"))
    )
    (net (code "48") (name "unconnected-(U1-(ADC1)PF1-Pad40)") (class "Default")
      (node (ref "U1") (pin "40") (pinfunction "(ADC1)PF1_40") (pintype "bidirectional"))
    )
    (net (code "49") (name "unconnected-(U1-(ADC4{slash}TCK)PF4-Pad39)") (class "Default")
      (node (ref "U1") (pin "39") (pinfunction "(ADC4/TCK)PF4_39") (pintype "bidirectional"))
    )
    (net (code "50") (name "unconnected-(U1-(ADC5{slash}TMS)PF5-Pad38)") (class "Default")
      (node (ref "U1") (pin "38") (pinfunction "(ADC5/TMS)PF5_38") (pintype "bidirectional"))
    )
    (net (code "51") (name "unconnected-(U1-(ADC6{slash}TDO)PF6-Pad37)") (class "Default")
      (node (ref "U1") (pin "37") (pinfunction "(ADC6/TDO)PF6_37") (pintype "bidirectional"))
    )
    (net (code "52") (name "unconnected-(U1-(ADC7{slash}TDI)PF7-Pad36)") (class "Default")
      (node (ref "U1") (pin "36") (pinfunction "(ADC7/TDI)PF7_36") (pintype "bidirectional"))
    )
    (net (code "53") (name "unconnected-(U1-(ADC11{slash}PCINT4)PB4-Pad28)") (class "Default")
      (node (ref "U1") (pin "28") (pinfunction "(ADC11/PCINT4)PB4_28") (pintype "bidirectional"))
    )
    (net (code "54") (name "unconnected-(U1-(ICP3{slash}CLK0{slash}OC4A)PC7-Pad32)") (class "Default")
      (node (ref "U1") (pin "32") (pinfunction "(ICP3/CLK0/OC4A)PC7_32") (pintype "bidirectional"))
    )
    (net (code "55") (name "unconnected-(U1-(OC3A{slash}#0C4A)PC6-Pad31)") (class "Default")
      (node (ref "U1") (pin "31") (pinfunction "(OC3A/#0C4A)PC6_31") (pintype "bidirectional"))
    )
    (net (code "56") (name "unconnected-(U1-(PCINT5{slash}OC1A{slash}#OC4B{slash}ADC12)PB5-Pad29)") (class "Default")
      (node (ref "U1") (pin "29") (pinfunction "(PCINT5/OC1A/#OC4B/ADC12)PB5_29") (pintype "bidirectional"))
    )
    (net (code "57") (name "unconnected-(U1-(PCINT6{slash}OC1B{slash}OC4B{slash}ADC13)PB6-Pad30)") (class "Default")
      (node (ref "U1") (pin "30") (pinfunction "(PCINT6/OC1B/OC4B/ADC13)PB6_30") (pintype "bidirectional"))
    )
    (net (code "58") (name "unconnected-(U1-(PCINT7{slash}OC0A{slash}OC1C{slash}#RTS)PB7-Pad12)") (class "Default")
      (node (ref "U1") (pin "12") (pinfunction "(PCINT7/OC0A/OC1C/#RTS)PB7_12") (pintype "bidirectional"))
    )
    (net (code "59") (name "unconnected-(U1-(SS{slash}PCINT0)PB0-Pad8)") (class "Default")
      (node (ref "U1") (pin "8") (pinfunction "(SS/PCINT0)PB0_8") (pintype "bidirectional"))
    )
    (net (code "60") (name "unconnected-(U1-RESET-Pad13)") (class "Default")
      (node (ref "U1") (pin "13") (pinfunction "RESET_13") (pintype "input"))
    )
    (net (code "61") (name "unconnected-(U3-NC{slash}FB-Pad4)") (class "Default")
      (node (ref "U3") (pin "4") (pinfunction "NC/FB_4") (pintype "passive"))
    )
    (net (code "62") (name "unconnected-(U4-AUX_CL-Pad7)") (class "Default")
      (node (ref "U4") (pin "7") (pinfunction "AUX_CL_7") (pintype "bidirectional"))
    )
    (net (code "63") (name "unconnected-(U4-AUX_DA-Pad6)") (class "Default")
      (node (ref "U4") (pin "6") (pinfunction "AUX_DA_6") (pintype "bidirectional"))
    )
  )
)
